# rfm12trx.net
KiCad netlist of a schematic drawn in EAGLE
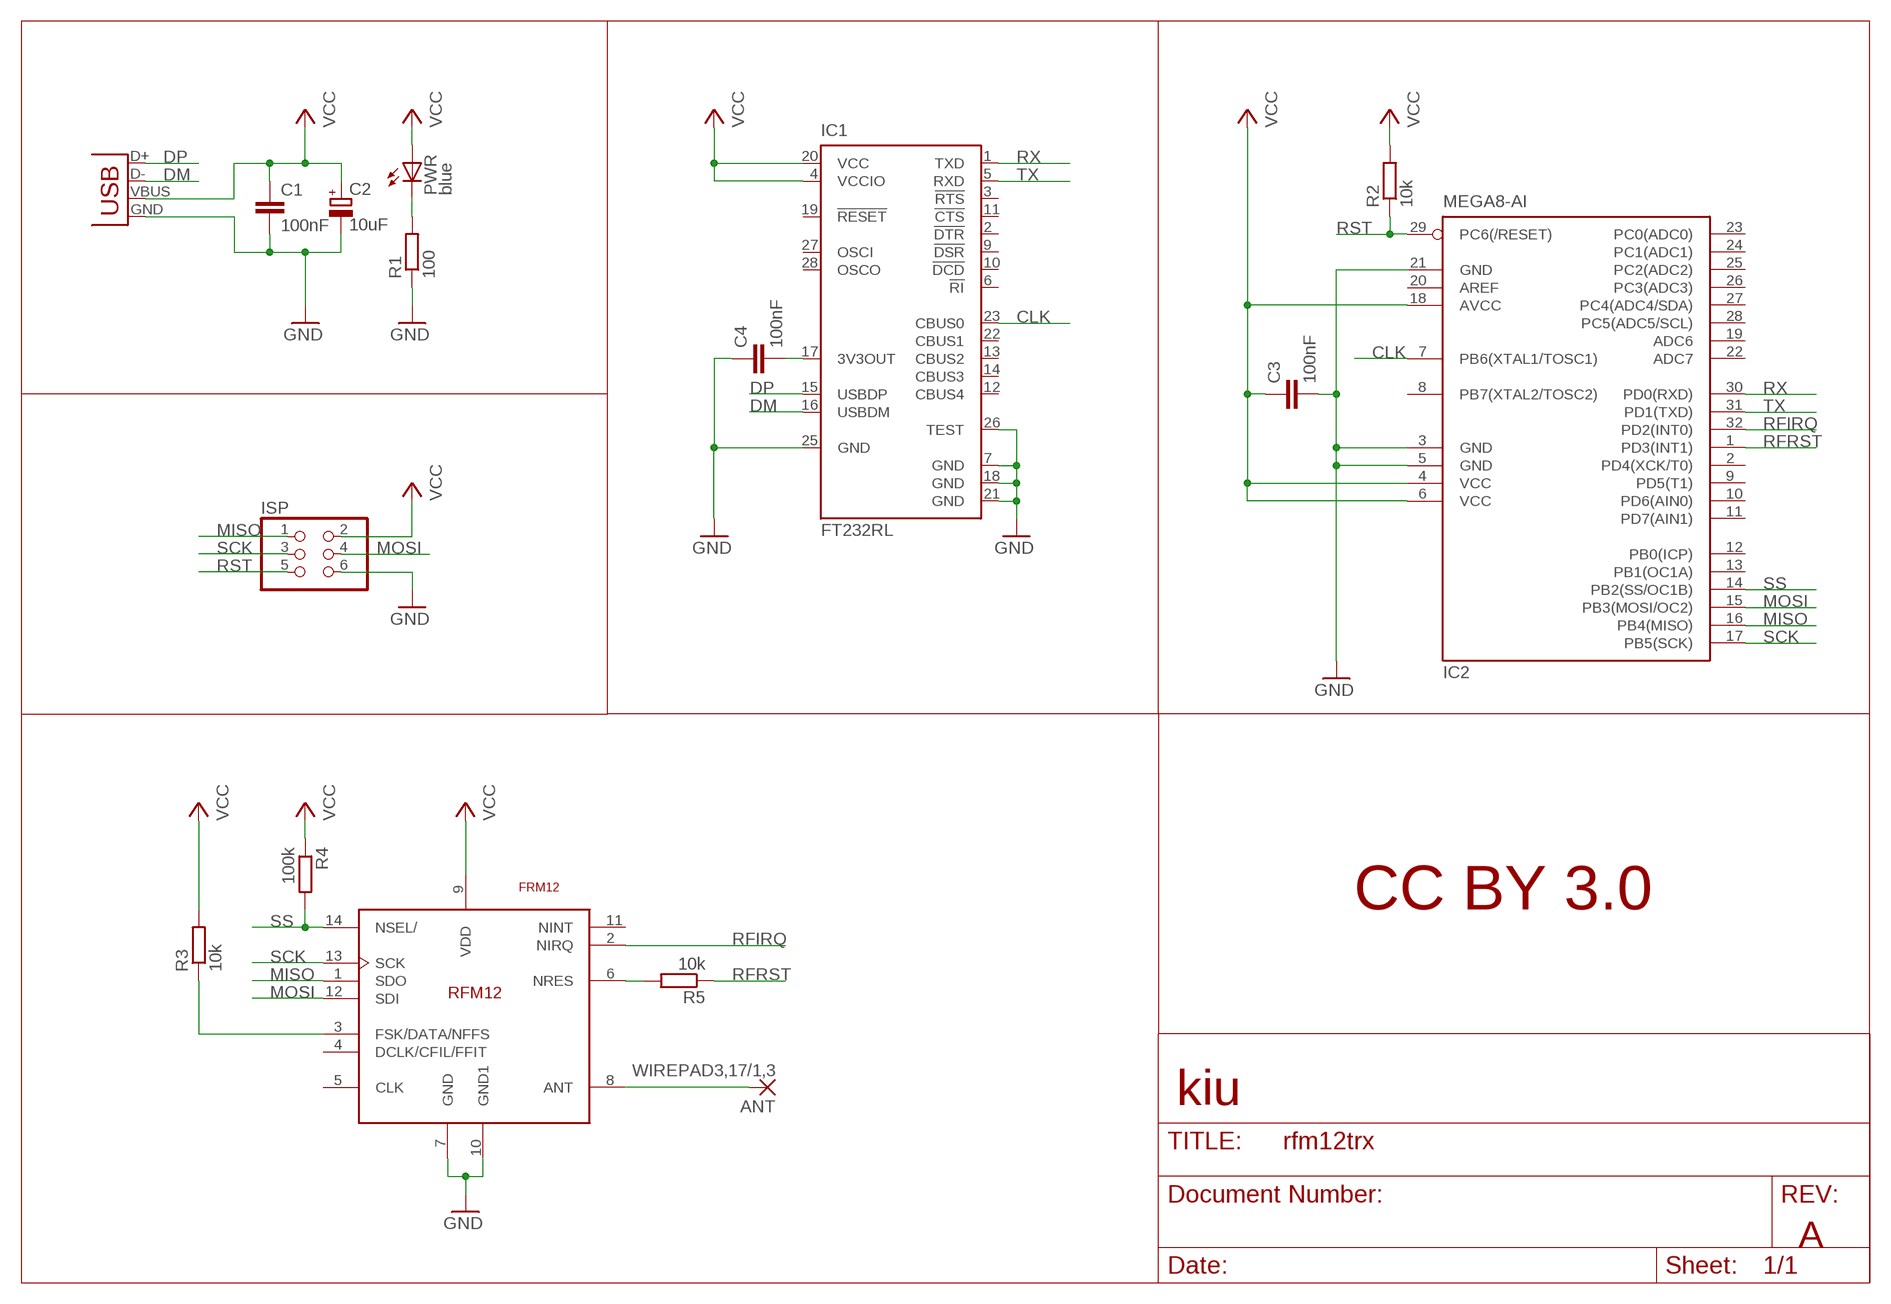
[diagram p0: schematic, sheet 1]

(export (version "E")
  (design (tool "Eeschema 10.0.6"))
  (components
    (comp (ref "ANT")
      (value "WIREPAD3,17/1,3")
      (footprint "eagle-import:3,17_1,3")
      (libsource (lib "eagle-import") (part "WIREPAD3,17/1,3"))
    )
    (comp (ref "C1")
      (value "100nF")
      (footprint "eagle-import:C0603")
      (libsource (lib "eagle-import") (part "C-EUC0603"))
    )
    (comp (ref "C2")
      (value "10uF")
      (footprint "eagle-import:CT3216")
      (libsource (lib "eagle-import") (part "CPOL-EUCT3216"))
    )
    (comp (ref "C3")
      (value "100nF")
      (footprint "eagle-import:C0603")
      (libsource (lib "eagle-import") (part "C-EUC0603"))
    )
    (comp (ref "C4")
      (value "100nF")
      (footprint "eagle-import:C0603")
      (libsource (lib "eagle-import") (part "C-EUC0603"))
    )
    (comp (ref "IC1")
      (value "FT232RL")
      (footprint "eagle-import:SSOP28")
      (libsource (lib "eagle-import") (part "FT232RL"))
    )
    (comp (ref "IC2")
      (value "MEGA8-AI")
      (footprint "eagle-import:TQFP32-08")
      (fields (field (name "MPN") "ATMEGA8-16AU"))
      (libsource (lib "eagle-import") (part "MEGA8-AI"))
    )
    (comp (ref "ISP")
      (value "PINHD-2X3")
      (footprint "eagle-import:2X03")
      (libsource (lib "eagle-import") (part "PINHD-2X3"))
    )
    (comp (ref "PWR")
      (value "blue")
      (footprint "eagle-import:CHIP-LED0805")
      (libsource (lib "eagle-import") (part "LEDCHIP-LED0805"))
    )
    (comp (ref "R1")
      (value "100")
      (footprint "eagle-import:R0603")
      (libsource (lib "eagle-import") (part "R-EU_R0603"))
    )
    (comp (ref "R2")
      (value "10k")
      (footprint "eagle-import:R0603")
      (libsource (lib "eagle-import") (part "R-EU_R0603"))
    )
    (comp (ref "R3")
      (value "10k")
      (footprint "eagle-import:R0603")
      (libsource (lib "eagle-import") (part "R-EU_R0603"))
    )
    (comp (ref "R4")
      (value "100k")
      (footprint "eagle-import:R0603")
      (libsource (lib "eagle-import") (part "R-EU_R0603"))
    )
    (comp (ref "R5")
      (value "10k")
      (footprint "eagle-import:R0603")
      (libsource (lib "eagle-import") (part "R-EU_R0603"))
    )
    (comp (ref "U$1")
      (value "FRM12")
      (footprint "eagle-import:RFM12")
      (libsource (lib "eagle-import") (part "FRM12"))
    )
    (comp (ref "X1")
      (value "USB-MICROB")
      (footprint "eagle-import:USB-MICROB")
      (libsource (lib "eagle-import") (part "USB-MICROB"))
    )
  )
  (nets
    (net (code "1") (name "/CLK") (class "Default")
      (node (ref "IC1") (pin "23") (pinfunction "CBUS0_23") (pintype "bidirectional"))
      (node (ref "IC2") (pin "7") (pinfunction "PB6(XTAL1/TOSC1)_7") (pintype "bidirectional"))
    )
    (net (code "2") (name "/DM") (class "Default")
      (node (ref "IC1") (pin "16") (pinfunction "USBDM_16") (pintype "bidirectional"))
      (node (ref "X1") (pin "D-") (pinfunction "D-_D-") (pintype "bidirectional"))
    )
    (net (code "3") (name "/DP") (class "Default")
      (node (ref "IC1") (pin "15") (pinfunction "USBDP_15") (pintype "bidirectional"))
      (node (ref "X1") (pin "D+") (pinfunction "D+_D+") (pintype "bidirectional"))
    )
    (net (code "4") (name "/MISO") (class "Default")
      (node (ref "IC2") (pin "16") (pinfunction "PB4(MISO)_16") (pintype "bidirectional"))
      (node (ref "ISP") (pin "1") (pinfunction "1_1") (pintype "passive"))
      (node (ref "U$1") (pin "1") (pinfunction "SDO_1") (pintype "output"))
    )
    (net (code "5") (name "/MOSI") (class "Default")
      (node (ref "IC2") (pin "15") (pinfunction "PB3(MOSI/OC2)_15") (pintype "bidirectional"))
      (node (ref "ISP") (pin "4") (pinfunction "4_4") (pintype "passive"))
      (node (ref "U$1") (pin "12") (pinfunction "SDI_12") (pintype "input"))
    )
    (net (code "6") (name "/RFIRQ") (class "Default")
      (node (ref "IC2") (pin "32") (pinfunction "PD2(INT0)_32") (pintype "bidirectional"))
      (node (ref "U$1") (pin "2") (pinfunction "NIRQ_2") (pintype "output"))
    )
    (net (code "7") (name "/RFRST") (class "Default")
      (node (ref "IC2") (pin "1") (pinfunction "PD3(INT1)_1") (pintype "bidirectional"))
      (node (ref "R5") (pin "1") (pinfunction "1_1") (pintype "passive"))
    )
    (net (code "8") (name "/RST") (class "Default")
      (node (ref "IC2") (pin "29") (pinfunction "PC6(/RESET)_29") (pintype "bidirectional"))
      (node (ref "ISP") (pin "5") (pinfunction "5_5") (pintype "passive"))
      (node (ref "R2") (pin "1") (pinfunction "1_1") (pintype "passive"))
    )
    (net (code "9") (name "/RX") (class "Default")
      (node (ref "IC1") (pin "1") (pinfunction "TXD_1") (pintype "output"))
      (node (ref "IC2") (pin "30") (pinfunction "PD0(RXD)_30") (pintype "bidirectional"))
    )
    (net (code "10") (name "/SCK") (class "Default")
      (node (ref "IC2") (pin "17") (pinfunction "PB5(SCK)_17") (pintype "bidirectional"))
      (node (ref "ISP") (pin "3") (pinfunction "3_3") (pintype "passive"))
      (node (ref "U$1") (pin "13") (pinfunction "SCK_13") (pintype "input"))
    )
    (net (code "11") (name "/SS") (class "Default")
      (node (ref "IC2") (pin "14") (pinfunction "PB2(SS/OC1B)_14") (pintype "bidirectional"))
      (node (ref "R4") (pin "2") (pinfunction "2_2") (pintype "passive"))
      (node (ref "U$1") (pin "14") (pinfunction "NSEL/_14") (pintype "input"))
    )
    (net (code "12") (name "/TX") (class "Default")
      (node (ref "IC1") (pin "5") (pinfunction "RXD_5") (pintype "input"))
      (node (ref "IC2") (pin "31") (pinfunction "PD1(TXD)_31") (pintype "bidirectional"))
    )
    (net (code "13") (name "GND") (class "Default")
      (node (ref "C1") (pin "2") (pinfunction "2_2") (pintype "passive"))
      (node (ref "C2") (pin "-") (pinfunction "-_-") (pintype "passive"))
      (node (ref "C3") (pin "2") (pinfunction "2_2") (pintype "passive"))
      (node (ref "C4") (pin "1") (pinfunction "1_1") (pintype "passive"))
      (node (ref "IC1") (pin "18") (pinfunction "GND_18") (pintype "power_in"))
      (node (ref "IC1") (pin "21") (pinfunction "GND_21") (pintype "power_in"))
      (node (ref "IC1") (pin "25") (pinfunction "GND_25") (pintype "power_in"))
      (node (ref "IC1") (pin "26") (pinfunction "TEST_26") (pintype "input"))
      (node (ref "IC1") (pin "7") (pinfunction "GND_7") (pintype "power_in"))
      (node (ref "IC2") (pin "21") (pinfunction "GND_21") (pintype "power_in"))
      (node (ref "IC2") (pin "3") (pinfunction "GND_3") (pintype "power_in"))
      (node (ref "IC2") (pin "5") (pinfunction "GND_5") (pintype "power_in"))
      (node (ref "ISP") (pin "6") (pinfunction "6_6") (pintype "passive"))
      (node (ref "R1") (pin "1") (pinfunction "1_1") (pintype "passive"))
      (node (ref "U$1") (pin "10") (pinfunction "GND1_10") (pintype "passive"))
      (node (ref "U$1") (pin "7") (pinfunction "GND_7") (pintype "passive"))
      (node (ref "X1") (pin "GND") (pinfunction "GND_GND") (pintype "bidirectional"))
    )
    (net (code "14") (name "Net-(ANT-P)") (class "Default")
      (node (ref "ANT") (pin "1") (pinfunction "P_1") (pintype "passive"))
      (node (ref "U$1") (pin "8") (pinfunction "ANT_8") (pintype "bidirectional"))
    )
    (net (code "15") (name "Net-(IC1-3V3OUT)") (class "Default")
      (node (ref "C4") (pin "2") (pinfunction "2_2") (pintype "passive"))
      (node (ref "IC1") (pin "17") (pinfunction "3V3OUT_17") (pintype "output"))
    )
    (net (code "16") (name "Net-(PWR-PadC)") (class "Default")
      (node (ref "PWR") (pin "C") (pinfunction "C_C") (pintype "passive"))
      (node (ref "R1") (pin "2") (pinfunction "2_2") (pintype "passive"))
    )
    (net (code "17") (name "Net-(U$1-FSK{slash}DATA{slash}NFFS)") (class "Default")
      (node (ref "R3") (pin "1") (pinfunction "1_1") (pintype "passive"))
      (node (ref "U$1") (pin "3") (pinfunction "FSK/DATA/NFFS_3") (pintype "bidirectional"))
    )
    (net (code "18") (name "Net-(U$1-NRES)") (class "Default")
      (node (ref "R5") (pin "2") (pinfunction "2_2") (pintype "passive"))
      (node (ref "U$1") (pin "6") (pinfunction "NRES_6") (pintype "bidirectional"))
    )
    (net (code "19") (name "VCC") (class "Default")
      (node (ref "C1") (pin "1") (pinfunction "1_1") (pintype "passive"))
      (node (ref "C2") (pin "+") (pinfunction "+_+") (pintype "passive"))
      (node (ref "C3") (pin "1") (pinfunction "1_1") (pintype "passive"))
      (node (ref "IC1") (pin "20") (pinfunction "VCC_20") (pintype "power_in"))
      (node (ref "IC1") (pin "4") (pinfunction "VCCIO_4") (pintype "power_in"))
      (node (ref "IC2") (pin "18") (pinfunction "AVCC_18") (pintype "power_in"))
      (node (ref "IC2") (pin "4") (pinfunction "VCC_4") (pintype "power_in"))
      (node (ref "IC2") (pin "6") (pinfunction "VCC_6") (pintype "power_in"))
      (node (ref "ISP") (pin "2") (pinfunction "2_2") (pintype "passive"))
      (node (ref "PWR") (pin "A") (pinfunction "A_A") (pintype "passive"))
      (node (ref "R2") (pin "2") (pinfunction "2_2") (pintype "passive"))
      (node (ref "R3") (pin "2") (pinfunction "2_2") (pintype "passive"))
      (node (ref "R4") (pin "1") (pinfunction "1_1") (pintype "passive"))
      (node (ref "U$1") (pin "9") (pinfunction "VDD_9") (pintype "power_in"))
      (node (ref "X1") (pin "VBUS") (pinfunction "VBUS_VBUS") (pintype "bidirectional"))
    )
    (net (code "20") (name "unconnected-(IC1-CBUS1-Pad22)") (class "Default")
      (node (ref "IC1") (pin "22") (pinfunction "CBUS1_22") (pintype "bidirectional"))
    )
    (net (code "21") (name "unconnected-(IC1-CBUS2-Pad13)") (class "Default")
      (node (ref "IC1") (pin "13") (pinfunction "CBUS2_13") (pintype "bidirectional"))
    )
    (net (code "22") (name "unconnected-(IC1-CBUS3-Pad14)") (class "Default")
      (node (ref "IC1") (pin "14") (pinfunction "CBUS3_14") (pintype "bidirectional"))
    )
    (net (code "23") (name "unconnected-(IC1-CBUS4-Pad12)") (class "Default")
      (node (ref "IC1") (pin "12") (pinfunction "CBUS4_12") (pintype "bidirectional"))
    )
    (net (code "24") (name "unconnected-(IC1-OSCI-Pad27)") (class "Default")
      (node (ref "IC1") (pin "27") (pinfunction "OSCI_27") (pintype "input"))
    )
    (net (code "25") (name "unconnected-(IC1-OSCO-Pad28)") (class "Default")
      (node (ref "IC1") (pin "28") (pinfunction "OSCO_28") (pintype "output"))
    )
    (net (code "26") (name "unconnected-(IC1-~{CTS}-Pad11)") (class "Default")
      (node (ref "IC1") (pin "11") (pinfunction "~{CTS}_11") (pintype "input"))
    )
    (net (code "27") (name "unconnected-(IC1-~{DCD}-Pad10)") (class "Default")
      (node (ref "IC1") (pin "10") (pinfunction "~{DCD}_10") (pintype "input"))
    )
    (net (code "28") (name "unconnected-(IC1-~{DSR}-Pad9)") (class "Default")
      (node (ref "IC1") (pin "9") (pinfunction "~{DSR}_9") (pintype "input"))
    )
    (net (code "29") (name "unconnected-(IC1-~{DTR}-Pad2)") (class "Default")
      (node (ref "IC1") (pin "2") (pinfunction "~{DTR}_2") (pintype "output"))
    )
    (net (code "30") (name "unconnected-(IC1-~{RESET}-Pad19)") (class "Default")
      (node (ref "IC1") (pin "19") (pinfunction "~{RESET}_19") (pintype "input"))
    )
    (net (code "31") (name "unconnected-(IC1-~{RI}-Pad6)") (class "Default")
      (node (ref "IC1") (pin "6") (pinfunction "~{RI}_6") (pintype "input"))
    )
    (net (code "32") (name "unconnected-(IC1-~{RTS}-Pad3)") (class "Default")
      (node (ref "IC1") (pin "3") (pinfunction "~{RTS}_3") (pintype "output"))
    )
    (net (code "33") (name "unconnected-(IC2-ADC6-Pad19)") (class "Default")
      (node (ref "IC2") (pin "19") (pinfunction "ADC6_19") (pintype "bidirectional"))
    )
    (net (code "34") (name "unconnected-(IC2-ADC7-Pad22)") (class "Default")
      (node (ref "IC2") (pin "22") (pinfunction "ADC7_22") (pintype "bidirectional"))
    )
    (net (code "35") (name "unconnected-(IC2-AREF-Pad20)") (class "Default")
      (node (ref "IC2") (pin "20") (pinfunction "AREF_20") (pintype "passive"))
    )
    (net (code "36") (name "unconnected-(IC2-PB0(ICP)-Pad12)") (class "Default")
      (node (ref "IC2") (pin "12") (pinfunction "PB0(ICP)_12") (pintype "bidirectional"))
    )
    (net (code "37") (name "unconnected-(IC2-PB1(OC1A)-Pad13)") (class "Default")
      (node (ref "IC2") (pin "13") (pinfunction "PB1(OC1A)_13") (pintype "bidirectional"))
    )
    (net (code "38") (name "unconnected-(IC2-PB7(XTAL2{slash}TOSC2)-Pad8)") (class "Default")
      (node (ref "IC2") (pin "8") (pinfunction "PB7(XTAL2/TOSC2)_8") (pintype "bidirectional"))
    )
    (net (code "39") (name "unconnected-(IC2-PC0(ADC0)-Pad23)") (class "Default")
      (node (ref "IC2") (pin "23") (pinfunction "PC0(ADC0)_23") (pintype "bidirectional"))
    )
    (net (code "40") (name "unconnected-(IC2-PC1(ADC1)-Pad24)") (class "Default")
      (node (ref "IC2") (pin "24") (pinfunction "PC1(ADC1)_24") (pintype "bidirectional"))
    )
    (net (code "41") (name "unconnected-(IC2-PC2(ADC2)-Pad25)") (class "Default")
      (node (ref "IC2") (pin "25") (pinfunction "PC2(ADC2)_25") (pintype "bidirectional"))
    )
    (net (code "42") (name "unconnected-(IC2-PC3(ADC3)-Pad26)") (class "Default")
      (node (ref "IC2") (pin "26") (pinfunction "PC3(ADC3)_26") (pintype "bidirectional"))
    )
    (net (code "43") (name "unconnected-(IC2-PC4(ADC4{slash}SDA)-Pad27)") (class "Default")
      (node (ref "IC2") (pin "27") (pinfunction "PC4(ADC4/SDA)_27") (pintype "bidirectional"))
    )
    (net (code "44") (name "unconnected-(IC2-PC5(ADC5{slash}SCL)-Pad28)") (class "Default")
      (node (ref "IC2") (pin "28") (pinfunction "PC5(ADC5/SCL)_28") (pintype "bidirectional"))
    )
    (net (code "45") (name "unconnected-(IC2-PD4(XCK{slash}T0)-Pad2)") (class "Default")
      (node (ref "IC2") (pin "2") (pinfunction "PD4(XCK/T0)_2") (pintype "bidirectional"))
    )
    (net (code "46") (name "unconnected-(IC2-PD5(T1)-Pad9)") (class "Default")
      (node (ref "IC2") (pin "9") (pinfunction "PD5(T1)_9") (pintype "bidirectional"))
    )
    (net (code "47") (name "unconnected-(IC2-PD6(AIN0)-Pad10)") (class "Default")
      (node (ref "IC2") (pin "10") (pinfunction "PD6(AIN0)_10") (pintype "bidirectional"))
    )
    (net (code "48") (name "unconnected-(IC2-PD7(AIN1)-Pad11)") (class "Default")
      (node (ref "IC2") (pin "11") (pinfunction "PD7(AIN1)_11") (pintype "bidirectional"))
    )
    (net (code "49") (name "unconnected-(U$1-CLK-Pad5)") (class "Default")
      (node (ref "U$1") (pin "5") (pinfunction "CLK_5") (pintype "output"))
    )
    (net (code "50") (name "unconnected-(U$1-DCLK{slash}CFIL{slash}FFIT-Pad4)") (class "Default")
      (node (ref "U$1") (pin "4") (pinfunction "DCLK/CFIL/FFIT_4") (pintype "bidirectional"))
    )
    (net (code "51") (name "unconnected-(U$1-NINT-Pad11)") (class "Default")
      (node (ref "U$1") (pin "11") (pinfunction "NINT_11") (pintype "bidirectional"))
    )
  )
)
